# v1_3.net
KiCad netlist of a schematic drawn in Altium Designer
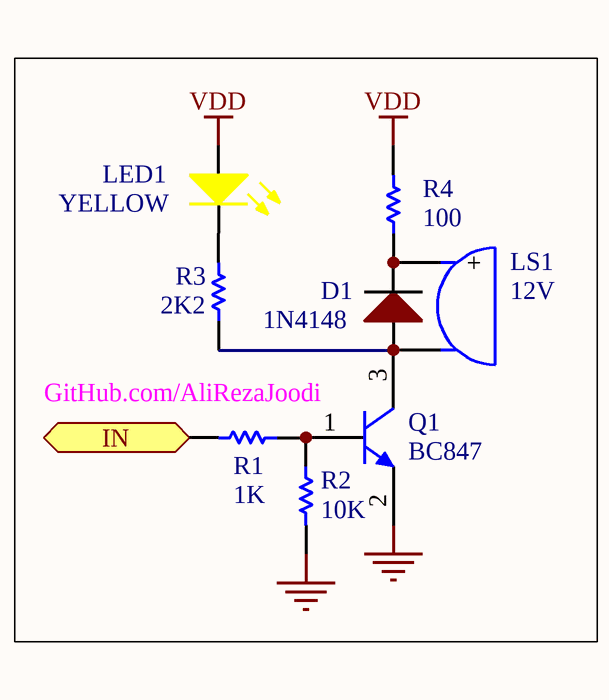
[diagram p0: v1.3.SchDoc]

(export (version "E")
  (design (tool "Eeschema 10.0.6"))
  (components
    (comp (ref "D1")
      (value "1N4148")
      (footprint "D_THD_AXIAL0.3_DO-35")
      (description "Diode,")
      (libsource (lib "Passive") (part "Diode_2Form"))
    )
    (comp (ref "LED1")
      (value "YELLOW")
      (footprint "LED_THD_3MM_YELLOW_R")
      (description "LED, Yellow")
      (fields (field (name "MANUFACTURER") "Generic Components") (field (name "PUBLISHER") "Altium Limited"))
      (libsource (lib "Display") (part "LED_YELLOW"))
    )
    (comp (ref "LS1")
      (value "12V")
      (footprint "RB_7.62mm")
      (description "Sounder")
      (fields (field (name "PUBLISHER") "Altium Limited"))
      (libsource (lib "Other_Myself") (part "Buzzer"))
    )
    (comp (ref "Q1")
      (value "BC847")
      (footprint "SOT23-3N")
      (description "Silicon Bipolar Transistor")
      (fields (field (name "Comment") "NPN"))
      (libsource (lib "my Libraries") (part "BC847"))
    )
    (comp (ref "R1")
      (value "1K")
      (footprint "0805")
      (description "Resistor")
      (fields (field (name "Comment") "Res1") (field (name "PUBLISHER") "Altium Limited"))
      (libsource (lib "Miscellaneous Devices") (part "Res1"))
    )
    (comp (ref "R2")
      (value "10K")
      (footprint "0805")
      (description "Resistor")
      (fields (field (name "Comment") "Res1") (field (name "PUBLISHER") "Altium Limited"))
      (libsource (lib "Miscellaneous Devices") (part "Res1"))
    )
    (comp (ref "R3")
      (value "2K2")
      (footprint "0805")
      (description "Resistor")
      (fields (field (name "PUBLISHER") "Altium Limited"))
      (libsource (lib "Miscellaneous Devices") (part "Res1"))
    )
    (comp (ref "R4")
      (value "100")
      (footprint "0805")
      (description "Resistor")
      (fields (field (name "Comment") "Res1") (field (name "PUBLISHER") "Altium Limited"))
      (libsource (lib "Miscellaneous Devices") (part "Res1"))
    )
  )
  (nets
    (net (code "1") (name "/IN") (class "Default")
      (node (ref "R1") (pin "2") (pinfunction "2_2") (pintype "passive"))
    )
    (net (code "2") (name "GND") (class "Default")
      (node (ref "Q1") (pin "2") (pinfunction "E_2") (pintype "passive"))
      (node (ref "R2") (pin "2") (pinfunction "2_2") (pintype "passive"))
    )
    (net (code "3") (name "Net-(D1-A)") (class "Default")
      (node (ref "D1") (pin "1") (pinfunction "A_1") (pintype "passive"))
      (node (ref "LS1") (pin "2") (pinfunction "B_2") (pintype "passive"))
      (node (ref "Q1") (pin "3") (pinfunction "C_3") (pintype "passive"))
      (node (ref "R3") (pin "1") (pinfunction "1_1") (pintype "passive"))
    )
    (net (code "4") (name "Net-(D1-K)") (class "Default")
      (node (ref "D1") (pin "2") (pinfunction "K_2") (pintype "passive"))
      (node (ref "LS1") (pin "1") (pinfunction "+_1") (pintype "passive"))
      (node (ref "R4") (pin "1") (pinfunction "1_1") (pintype "passive"))
    )
    (net (code "5") (name "Net-(LED1-K)") (class "Default")
      (node (ref "LED1") (pin "2") (pinfunction "K_2") (pintype "passive"))
      (node (ref "R3") (pin "2") (pinfunction "2_2") (pintype "passive"))
    )
    (net (code "6") (name "Net-(Q1-B)") (class "Default")
      (node (ref "Q1") (pin "1") (pinfunction "B_1") (pintype "passive"))
      (node (ref "R1") (pin "1") (pinfunction "1_1") (pintype "passive"))
      (node (ref "R2") (pin "1") (pinfunction "1_1") (pintype "passive"))
    )
    (net (code "7") (name "VDD") (class "Default")
      (node (ref "LED1") (pin "1") (pinfunction "A_1") (pintype "passive"))
      (node (ref "R4") (pin "2") (pinfunction "2_2") (pintype "passive"))
    )
  )
)
